# SparkFun_Ardumoto_v14.net
KiCad netlist of a schematic drawn in EAGLE
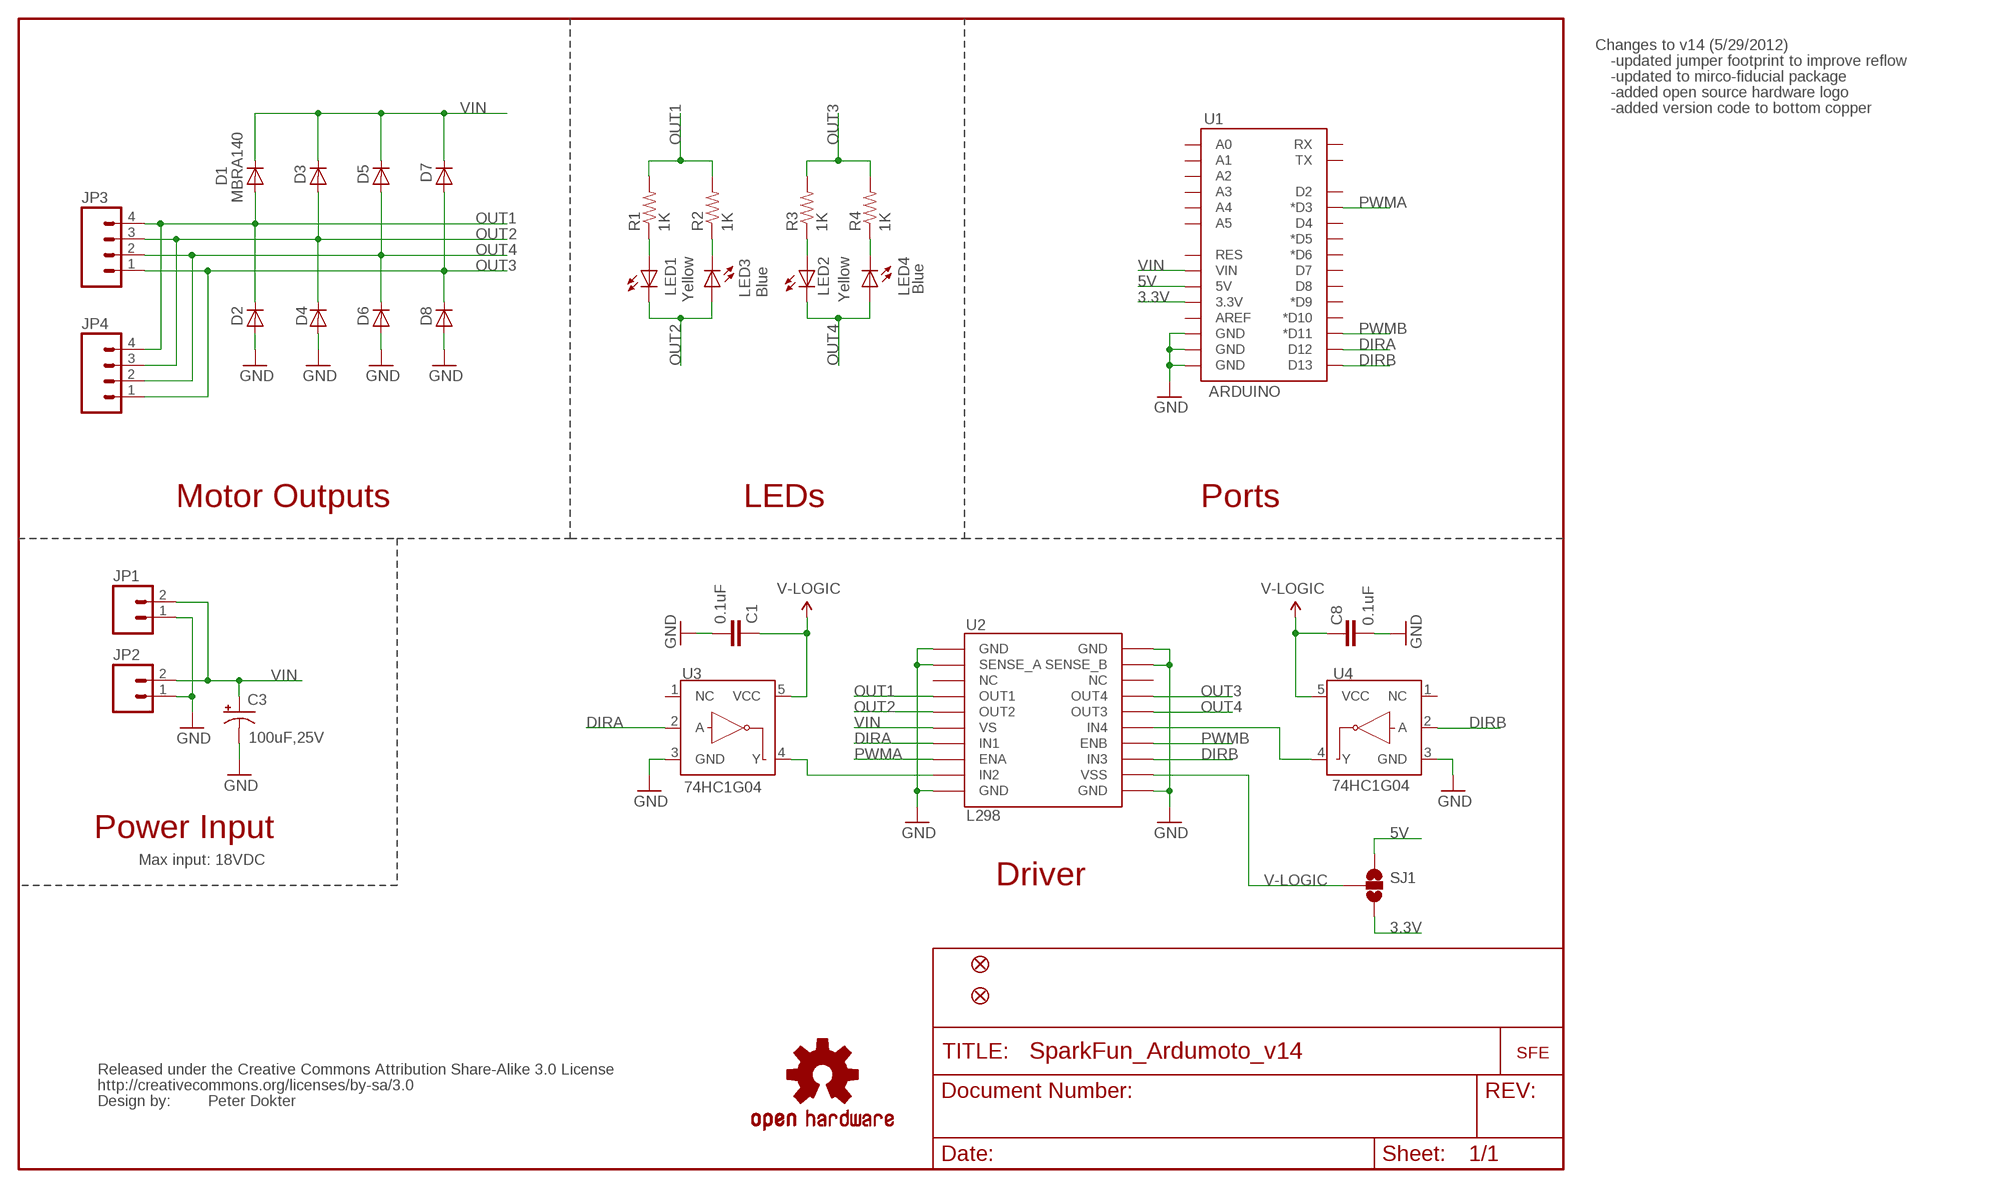
[diagram p0: schematic, sheet 1]

(export (version "E")
  (design (tool "Eeschema 10.0.6"))
  (components
    (comp (ref "C1")
      (value "0.1uF")
      (footprint "eagle-import:0402-CAP")
      (libsource (lib "eagle-import") (part "CAP0402-CAP"))
    )
    (comp (ref "C3")
      (value "100uF,25V")
      (footprint "eagle-import:NIPPON_F80")
      (libsource (lib "eagle-import") (part "CAP_POLF80"))
    )
    (comp (ref "C8")
      (value "0.1uF")
      (footprint "eagle-import:0402-CAP")
      (libsource (lib "eagle-import") (part "CAP0402-CAP"))
    )
    (comp (ref "D1")
      (value "MBRA140")
      (footprint "eagle-import:SMA-DIODE")
      (libsource (lib "eagle-import") (part "DIODESMA"))
    )
    (comp (ref "D2")
      (value "MBRA140")
      (footprint "eagle-import:SMA-DIODE")
      (libsource (lib "eagle-import") (part "DIODESMA"))
    )
    (comp (ref "D3")
      (value "MBRA140")
      (footprint "eagle-import:SMA-DIODE")
      (libsource (lib "eagle-import") (part "DIODESMA"))
    )
    (comp (ref "D4")
      (value "MBRA140")
      (footprint "eagle-import:SMA-DIODE")
      (libsource (lib "eagle-import") (part "DIODESMA"))
    )
    (comp (ref "D5")
      (value "MBRA140")
      (footprint "eagle-import:SMA-DIODE")
      (libsource (lib "eagle-import") (part "DIODESMA"))
    )
    (comp (ref "D6")
      (value "MBRA140")
      (footprint "eagle-import:SMA-DIODE")
      (libsource (lib "eagle-import") (part "DIODESMA"))
    )
    (comp (ref "D7")
      (value "MBRA140")
      (footprint "eagle-import:SMA-DIODE")
      (libsource (lib "eagle-import") (part "DIODESMA"))
    )
    (comp (ref "D8")
      (value "MBRA140")
      (footprint "eagle-import:SMA-DIODE")
      (libsource (lib "eagle-import") (part "DIODESMA"))
    )
    (comp (ref "JP1")
      (value "M02PTH")
      (footprint "eagle-import:1X02")
      (libsource (lib "eagle-import") (part "M02PTH"))
    )
    (comp (ref "JP2")
      (value "M023.5MM")
      (footprint "eagle-import:SCREWTERMINAL-3.5MM-2")
      (libsource (lib "eagle-import") (part "M023.5MM"))
    )
    (comp (ref "JP3")
      (value "M04SCREW")
      (footprint "eagle-import:SCREWTERMINAL-3.5MM-4")
      (libsource (lib "eagle-import") (part "M04SCREW"))
    )
    (comp (ref "JP4")
      (value "M04PTH")
      (footprint "eagle-import:1X04")
      (libsource (lib "eagle-import") (part "M04PTH"))
    )
    (comp (ref "JP5")
      (value "FIDUCIALUFIDUCIAL")
      (footprint "eagle-import:MICRO-FIDUCIAL")
      (libsource (lib "eagle-import") (part "FIDUCIALUFIDUCIAL"))
    )
    (comp (ref "JP6")
      (value "FIDUCIALUFIDUCIAL")
      (footprint "eagle-import:MICRO-FIDUCIAL")
      (libsource (lib "eagle-import") (part "FIDUCIALUFIDUCIAL"))
    )
    (comp (ref "LED1")
      (value "Yellow")
      (footprint "eagle-import:LED-0603")
      (libsource (lib "eagle-import") (part "LED0603"))
    )
    (comp (ref "LED2")
      (value "Yellow")
      (footprint "eagle-import:LED-0603")
      (libsource (lib "eagle-import") (part "LED0603"))
    )
    (comp (ref "LED3")
      (value "Blue")
      (footprint "eagle-import:LED-0603")
      (libsource (lib "eagle-import") (part "LED0603"))
    )
    (comp (ref "LED4")
      (value "Blue")
      (footprint "eagle-import:LED-0603")
      (libsource (lib "eagle-import") (part "LED0603"))
    )
    (comp (ref "R1")
      (value "1K")
      (footprint "eagle-import:0402-RES")
      (libsource (lib "eagle-import") (part "RESISTOR0402-RES"))
    )
    (comp (ref "R2")
      (value "1K")
      (footprint "eagle-import:0402-RES")
      (libsource (lib "eagle-import") (part "RESISTOR0402-RES"))
    )
    (comp (ref "R3")
      (value "1K")
      (footprint "eagle-import:0402-RES")
      (libsource (lib "eagle-import") (part "RESISTOR0402-RES"))
    )
    (comp (ref "R4")
      (value "1K")
      (footprint "eagle-import:0402-RES")
      (libsource (lib "eagle-import") (part "RESISTOR0402-RES"))
    )
    (comp (ref "SJ1")
      (value "SOLDERJUMPER_2WAYPASTE1&2")
      (footprint "eagle-import:SJ_3_PASTE1&2")
      (libsource (lib "eagle-import") (part "SOLDERJUMPER_2WAYPASTE1&2"))
    )
    (comp (ref "U$1")
      (value "OSHW-LOGOS")
      (footprint "eagle-import:OSHW-LOGO-S")
      (libsource (lib "eagle-import") (part "OSHW-LOGOS"))
    )
    (comp (ref "U$10")
      (value "LOGO-SFENEW")
      (footprint "eagle-import:SFE-NEW-WEBLOGO")
      (libsource (lib "eagle-import") (part "LOGO-SFENEW"))
    )
    (comp (ref "U$11")
      (value "CREATIVE_COMMONS")
      (footprint "eagle-import:CREATIVE_COMMONS")
      (libsource (lib "eagle-import") (part "CREATIVE_COMMONS"))
    )
    (comp (ref "U1")
      (value "ARDUINO")
      (footprint "eagle-import:DUEMILANOVE_SHIELD_NOLABELS")
      (libsource (lib "eagle-import") (part "ARDUINO_SHIELDNOLABELS"))
    )
    (comp (ref "U2")
      (value "L298")
      (footprint "eagle-import:POWERSO20")
      (libsource (lib "eagle-import") (part "L298_BRIDGE_DRIVER"))
    )
    (comp (ref "U3")
      (value "74HC1G04")
      (footprint "eagle-import:SC70")
      (libsource (lib "eagle-import") (part "INVERTER{dblquote}{dblquote}"))
    )
    (comp (ref "U4")
      (value "74HC1G04")
      (footprint "eagle-import:SC70")
      (libsource (lib "eagle-import") (part "INVERTER{dblquote}{dblquote}"))
    )
  )
  (nets
    (net (code "1") (name "/3.3V") (class "Default")
      (node (ref "SJ1") (pin "3") (pinfunction "3_3") (pintype "passive"))
      (node (ref "U1") (pin "3.3V") (pinfunction "3.3V_3.3V") (pintype "bidirectional"))
    )
    (net (code "2") (name "/5V") (class "Default")
      (node (ref "SJ1") (pin "1") (pinfunction "1_1") (pintype "passive"))
      (node (ref "U1") (pin "5V") (pinfunction "5V_5V") (pintype "bidirectional"))
    )
    (net (code "3") (name "/DIRA") (class "Default")
      (node (ref "U1") (pin "D12") (pinfunction "D12_D12") (pintype "bidirectional"))
      (node (ref "U2") (pin "7") (pinfunction "IN1_7") (pintype "bidirectional"))
      (node (ref "U3") (pin "2") (pinfunction "A_2") (pintype "bidirectional"))
    )
    (net (code "4") (name "/DIRB") (class "Default")
      (node (ref "U1") (pin "D13") (pinfunction "D13_D13") (pintype "bidirectional"))
      (node (ref "U2") (pin "13") (pinfunction "IN3_13") (pintype "bidirectional"))
      (node (ref "U4") (pin "2") (pinfunction "A_2") (pintype "bidirectional"))
    )
    (net (code "5") (name "/OUT1") (class "Default")
      (node (ref "D1") (pin "A") (pinfunction "A_A") (pintype "passive"))
      (node (ref "D2") (pin "C") (pinfunction "C_C") (pintype "passive"))
      (node (ref "JP3") (pin "4") (pinfunction "4_4") (pintype "passive"))
      (node (ref "JP4") (pin "4") (pinfunction "4_4") (pintype "passive"))
      (node (ref "R1") (pin "2") (pinfunction "2_2") (pintype "passive"))
      (node (ref "R2") (pin "2") (pinfunction "2_2") (pintype "passive"))
      (node (ref "U2") (pin "4") (pinfunction "OUT1_4") (pintype "bidirectional"))
    )
    (net (code "6") (name "/OUT2") (class "Default")
      (node (ref "D3") (pin "A") (pinfunction "A_A") (pintype "passive"))
      (node (ref "D4") (pin "C") (pinfunction "C_C") (pintype "passive"))
      (node (ref "JP3") (pin "3") (pinfunction "3_3") (pintype "passive"))
      (node (ref "JP4") (pin "3") (pinfunction "3_3") (pintype "passive"))
      (node (ref "LED1") (pin "C") (pinfunction "C_C") (pintype "passive"))
      (node (ref "LED3") (pin "A") (pinfunction "A_A") (pintype "passive"))
      (node (ref "U2") (pin "5") (pinfunction "OUT2_5") (pintype "bidirectional"))
    )
    (net (code "7") (name "/OUT3") (class "Default")
      (node (ref "D7") (pin "A") (pinfunction "A_A") (pintype "passive"))
      (node (ref "D8") (pin "C") (pinfunction "C_C") (pintype "passive"))
      (node (ref "JP3") (pin "1") (pinfunction "1_1") (pintype "passive"))
      (node (ref "JP4") (pin "1") (pinfunction "1_1") (pintype "passive"))
      (node (ref "R3") (pin "2") (pinfunction "2_2") (pintype "passive"))
      (node (ref "R4") (pin "2") (pinfunction "2_2") (pintype "passive"))
      (node (ref "U2") (pin "17") (pinfunction "OUT4_17") (pintype "bidirectional"))
    )
    (net (code "8") (name "/OUT4") (class "Default")
      (node (ref "D5") (pin "A") (pinfunction "A_A") (pintype "passive"))
      (node (ref "D6") (pin "C") (pinfunction "C_C") (pintype "passive"))
      (node (ref "JP3") (pin "2") (pinfunction "2_2") (pintype "passive"))
      (node (ref "JP4") (pin "2") (pinfunction "2_2") (pintype "passive"))
      (node (ref "LED2") (pin "C") (pinfunction "C_C") (pintype "passive"))
      (node (ref "LED4") (pin "A") (pinfunction "A_A") (pintype "passive"))
      (node (ref "U2") (pin "16") (pinfunction "OUT3_16") (pintype "bidirectional"))
    )
    (net (code "9") (name "/PWMA") (class "Default")
      (node (ref "U1") (pin "D3") (pinfunction "*D3_D3") (pintype "bidirectional"))
      (node (ref "U2") (pin "8") (pinfunction "ENA_8") (pintype "bidirectional"))
    )
    (net (code "10") (name "/PWMB") (class "Default")
      (node (ref "U1") (pin "D11") (pinfunction "*D11_D11") (pintype "bidirectional"))
      (node (ref "U2") (pin "14") (pinfunction "ENB_14") (pintype "bidirectional"))
    )
    (net (code "11") (name "/VIN") (class "Default")
      (node (ref "C3") (pin "+") (pinfunction "+_+") (pintype "passive"))
      (node (ref "D1") (pin "C") (pinfunction "C_C") (pintype "passive"))
      (node (ref "D3") (pin "C") (pinfunction "C_C") (pintype "passive"))
      (node (ref "D5") (pin "C") (pinfunction "C_C") (pintype "passive"))
      (node (ref "D7") (pin "C") (pinfunction "C_C") (pintype "passive"))
      (node (ref "JP1") (pin "2") (pinfunction "2_2") (pintype "passive"))
      (node (ref "JP2") (pin "2") (pinfunction "2_2") (pintype "passive"))
      (node (ref "U1") (pin "VIN") (pinfunction "VIN_VIN") (pintype "bidirectional"))
      (node (ref "U2") (pin "6") (pinfunction "VS_6") (pintype "bidirectional"))
    )
    (net (code "12") (name "GND") (class "Default")
      (node (ref "C1") (pin "2") (pinfunction "2_2") (pintype "passive"))
      (node (ref "C3") (pin "-") (pinfunction "-_-") (pintype "passive"))
      (node (ref "C8") (pin "2") (pinfunction "2_2") (pintype "passive"))
      (node (ref "D2") (pin "A") (pinfunction "A_A") (pintype "passive"))
      (node (ref "D4") (pin "A") (pinfunction "A_A") (pintype "passive"))
      (node (ref "D6") (pin "A") (pinfunction "A_A") (pintype "passive"))
      (node (ref "D8") (pin "A") (pinfunction "A_A") (pintype "passive"))
      (node (ref "JP1") (pin "1") (pinfunction "1_1") (pintype "passive"))
      (node (ref "JP2") (pin "1") (pinfunction "1_1") (pintype "passive"))
      (node (ref "U1") (pin "GND@0") (pinfunction "GND_GND@0") (pintype "bidirectional"))
      (node (ref "U1") (pin "GND@1") (pinfunction "GND_GND@1") (pintype "bidirectional"))
      (node (ref "U1") (pin "GND@2") (pinfunction "GND_GND@2") (pintype "bidirectional"))
      (node (ref "U2") (pin "1") (pinfunction "GND_1") (pintype "bidirectional"))
      (node (ref "U2") (pin "10") (pinfunction "GND_10") (pintype "bidirectional"))
      (node (ref "U2") (pin "11") (pinfunction "GND_11") (pintype "bidirectional"))
      (node (ref "U2") (pin "19") (pinfunction "SENSE_B_19") (pintype "bidirectional"))
      (node (ref "U2") (pin "2") (pinfunction "SENSE_A_2") (pintype "bidirectional"))
      (node (ref "U2") (pin "20") (pinfunction "GND_20") (pintype "bidirectional"))
      (node (ref "U3") (pin "3") (pinfunction "GND_3") (pintype "bidirectional"))
      (node (ref "U4") (pin "3") (pinfunction "GND_3") (pintype "bidirectional"))
    )
    (net (code "13") (name "Net-(LED1-PadA)") (class "Default")
      (node (ref "LED1") (pin "A") (pinfunction "A_A") (pintype "passive"))
      (node (ref "R1") (pin "1") (pinfunction "1_1") (pintype "passive"))
    )
    (net (code "14") (name "Net-(LED2-PadA)") (class "Default")
      (node (ref "LED2") (pin "A") (pinfunction "A_A") (pintype "passive"))
      (node (ref "R3") (pin "1") (pinfunction "1_1") (pintype "passive"))
    )
    (net (code "15") (name "Net-(LED3-PadC)") (class "Default")
      (node (ref "LED3") (pin "C") (pinfunction "C_C") (pintype "passive"))
      (node (ref "R2") (pin "1") (pinfunction "1_1") (pintype "passive"))
    )
    (net (code "16") (name "Net-(LED4-PadC)") (class "Default")
      (node (ref "LED4") (pin "C") (pinfunction "C_C") (pintype "passive"))
      (node (ref "R4") (pin "1") (pinfunction "1_1") (pintype "passive"))
    )
    (net (code "17") (name "Net-(U2-IN2)") (class "Default")
      (node (ref "U2") (pin "9") (pinfunction "IN2_9") (pintype "bidirectional"))
      (node (ref "U3") (pin "4") (pinfunction "Y_4") (pintype "bidirectional"))
    )
    (net (code "18") (name "Net-(U2-IN4)") (class "Default")
      (node (ref "U2") (pin "15") (pinfunction "IN4_15") (pintype "bidirectional"))
      (node (ref "U4") (pin "4") (pinfunction "Y_4") (pintype "bidirectional"))
    )
    (net (code "19") (name "V-LOGIC") (class "Default")
      (node (ref "C1") (pin "1") (pinfunction "1_1") (pintype "passive"))
      (node (ref "C8") (pin "1") (pinfunction "1_1") (pintype "passive"))
      (node (ref "SJ1") (pin "2") (pinfunction "2_2") (pintype "passive"))
      (node (ref "U2") (pin "12") (pinfunction "VSS_12") (pintype "bidirectional"))
      (node (ref "U3") (pin "5") (pinfunction "VCC_5") (pintype "bidirectional"))
      (node (ref "U4") (pin "5") (pinfunction "VCC_5") (pintype "bidirectional"))
    )
    (net (code "20") (name "unconnected-(U1-*D5-PadD5)") (class "Default")
      (node (ref "U1") (pin "D5") (pinfunction "*D5_D5") (pintype "bidirectional"))
    )
    (net (code "21") (name "unconnected-(U1-*D6-PadD6)") (class "Default")
      (node (ref "U1") (pin "D6") (pinfunction "*D6_D6") (pintype "bidirectional"))
    )
    (net (code "22") (name "unconnected-(U1-*D9-PadD9)") (class "Default")
      (node (ref "U1") (pin "D9") (pinfunction "*D9_D9") (pintype "bidirectional"))
    )
    (net (code "23") (name "unconnected-(U1-*D10-PadD10)") (class "Default")
      (node (ref "U1") (pin "D10") (pinfunction "*D10_D10") (pintype "bidirectional"))
    )
    (net (code "24") (name "unconnected-(U1-PadA0)") (class "Default")
      (node (ref "U1") (pin "A0") (pinfunction "A0_A0") (pintype "bidirectional"))
    )
    (net (code "25") (name "unconnected-(U1-PadA1)") (class "Default")
      (node (ref "U1") (pin "A1") (pinfunction "A1_A1") (pintype "bidirectional"))
    )
    (net (code "26") (name "unconnected-(U1-PadA2)") (class "Default")
      (node (ref "U1") (pin "A2") (pinfunction "A2_A2") (pintype "bidirectional"))
    )
    (net (code "27") (name "unconnected-(U1-PadA3)") (class "Default")
      (node (ref "U1") (pin "A3") (pinfunction "A3_A3") (pintype "bidirectional"))
    )
    (net (code "28") (name "unconnected-(U1-PadA4)") (class "Default")
      (node (ref "U1") (pin "A4") (pinfunction "A4_A4") (pintype "bidirectional"))
    )
    (net (code "29") (name "unconnected-(U1-PadA5)") (class "Default")
      (node (ref "U1") (pin "A5") (pinfunction "A5_A5") (pintype "bidirectional"))
    )
    (net (code "30") (name "unconnected-(U1-PadAREF)") (class "Default")
      (node (ref "U1") (pin "AREF") (pinfunction "AREF_AREF") (pintype "bidirectional"))
    )
    (net (code "31") (name "unconnected-(U1-PadD2)") (class "Default")
      (node (ref "U1") (pin "D2") (pinfunction "D2_D2") (pintype "bidirectional"))
    )
    (net (code "32") (name "unconnected-(U1-PadD4)") (class "Default")
      (node (ref "U1") (pin "D4") (pinfunction "D4_D4") (pintype "bidirectional"))
    )
    (net (code "33") (name "unconnected-(U1-PadD7)") (class "Default")
      (node (ref "U1") (pin "D7") (pinfunction "D7_D7") (pintype "bidirectional"))
    )
    (net (code "34") (name "unconnected-(U1-PadD8)") (class "Default")
      (node (ref "U1") (pin "D8") (pinfunction "D8_D8") (pintype "bidirectional"))
    )
    (net (code "35") (name "unconnected-(U1-PadRES)") (class "Default")
      (node (ref "U1") (pin "RES") (pinfunction "RES_RES") (pintype "bidirectional"))
    )
    (net (code "36") (name "unconnected-(U1-PadRX)") (class "Default")
      (node (ref "U1") (pin "RX") (pinfunction "RX_RX") (pintype "bidirectional"))
    )
    (net (code "37") (name "unconnected-(U1-PadTX)") (class "Default")
      (node (ref "U1") (pin "TX") (pinfunction "TX_TX") (pintype "bidirectional"))
    )
    (net (code "38") (name "unconnected-(U2-NC-Pad3)") (class "Default")
      (node (ref "U2") (pin "3") (pinfunction "NC_3") (pintype "bidirectional"))
    )
    (net (code "39") (name "unconnected-(U2-NC-Pad18)") (class "Default")
      (node (ref "U2") (pin "18") (pinfunction "NC_18") (pintype "bidirectional"))
    )
    (net (code "40") (name "unconnected-(U3-NC-Pad1)") (class "Default")
      (node (ref "U3") (pin "1") (pinfunction "NC_1") (pintype "bidirectional"))
    )
    (net (code "41") (name "unconnected-(U4-NC-Pad1)") (class "Default")
      (node (ref "U4") (pin "1") (pinfunction "NC_1") (pintype "bidirectional"))
    )
  )
)
